# main.net
KiCad netlist of a schematic drawn in EAGLE
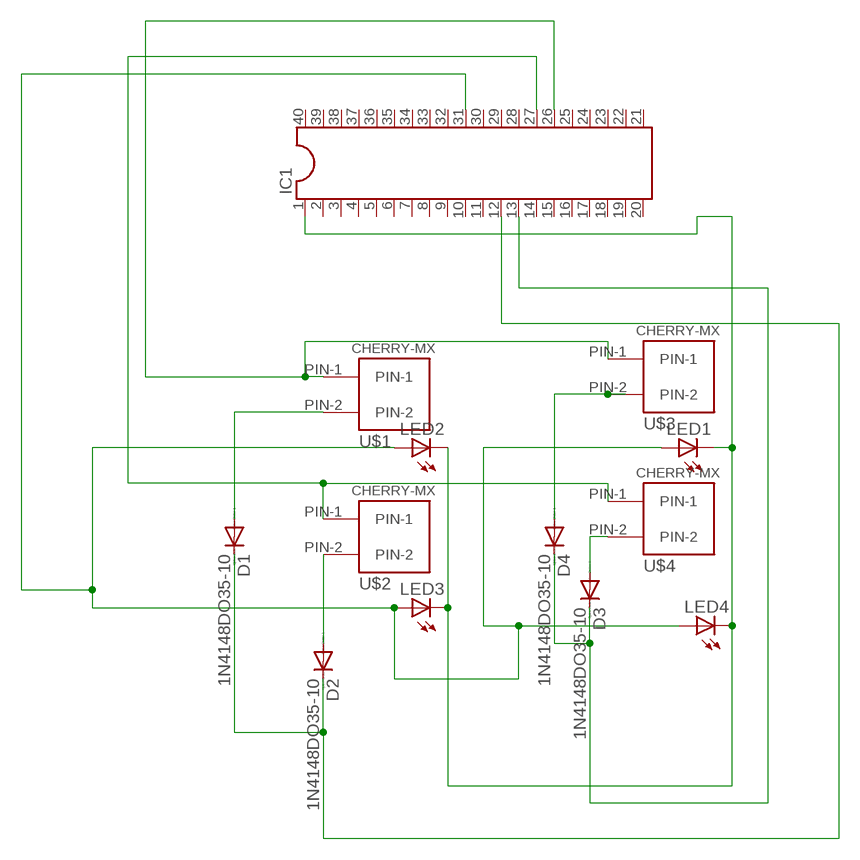
[diagram p0: schematic, sheet 1]

(export (version "E")
  (design (tool "Eeschema 10.0.6"))
  (components
    (comp (ref "D1")
      (value "1N4148DO35-10")
      (footprint "eagle-import:DO35-10")
      (libsource (lib "eagle-import") (part "1N4148DO35-10"))
    )
    (comp (ref "D2")
      (value "1N4148DO35-10")
      (footprint "eagle-import:DO35-10")
      (libsource (lib "eagle-import") (part "1N4148DO35-10"))
    )
    (comp (ref "D3")
      (value "1N4148DO35-10")
      (footprint "eagle-import:DO35-10")
      (libsource (lib "eagle-import") (part "1N4148DO35-10"))
    )
    (comp (ref "D4")
      (value "1N4148DO35-10")
      (footprint "eagle-import:DO35-10")
      (libsource (lib "eagle-import") (part "1N4148DO35-10"))
    )
    (comp (ref "IC1")
      (value "DIL40")
      (footprint "eagle-import:DIL40")
      (libsource (lib "eagle-import") (part "DIL40"))
    )
    (comp (ref "LED1")
      (value "LED3MM")
      (footprint "eagle-import:LED3MM")
      (libsource (lib "eagle-import") (part "LED3MM"))
    )
    (comp (ref "LED2")
      (value "LED3MM")
      (footprint "eagle-import:LED3MM")
      (libsource (lib "eagle-import") (part "LED3MM"))
    )
    (comp (ref "LED3")
      (value "LED3MM")
      (footprint "eagle-import:LED3MM")
      (libsource (lib "eagle-import") (part "LED3MM"))
    )
    (comp (ref "LED4")
      (value "LED3MM")
      (footprint "eagle-import:LED3MM")
      (libsource (lib "eagle-import") (part "LED3MM"))
    )
    (comp (ref "U$1")
      (value "CHERRY-MX-I")
      (footprint "eagle-import:CHERRY-MX-I")
      (libsource (lib "eagle-import") (part "CHERRY-MX-I"))
    )
    (comp (ref "U$2")
      (value "CHERRY-MX-I")
      (footprint "eagle-import:CHERRY-MX-I")
      (libsource (lib "eagle-import") (part "CHERRY-MX-I"))
    )
    (comp (ref "U$3")
      (value "CHERRY-MX-I")
      (footprint "eagle-import:CHERRY-MX-I")
      (libsource (lib "eagle-import") (part "CHERRY-MX-I"))
    )
    (comp (ref "U$4")
      (value "CHERRY-MX-I")
      (footprint "eagle-import:CHERRY-MX-I")
      (libsource (lib "eagle-import") (part "CHERRY-MX-I"))
    )
  )
  (nets
    (net (code "1") (name "Net-(D1-PadA)") (class "Default")
      (node (ref "D1") (pin "A") (pinfunction "A_A") (pintype "passive"))
      (node (ref "U$1") (pin "PIN-2") (pinfunction "PIN-2_PIN-2") (pintype "bidirectional"))
    )
    (net (code "2") (name "Net-(D1-PadC)") (class "Default")
      (node (ref "D1") (pin "C") (pinfunction "C_C") (pintype "passive"))
      (node (ref "D2") (pin "C") (pinfunction "C_C") (pintype "passive"))
      (node (ref "IC1") (pin "12") (pinfunction "12_12") (pintype "passive"))
    )
    (net (code "3") (name "Net-(D2-PadA)") (class "Default")
      (node (ref "D2") (pin "A") (pinfunction "A_A") (pintype "passive"))
      (node (ref "U$2") (pin "PIN-2") (pinfunction "PIN-2_PIN-2") (pintype "bidirectional"))
    )
    (net (code "4") (name "Net-(D3-PadA)") (class "Default")
      (node (ref "D3") (pin "A") (pinfunction "A_A") (pintype "passive"))
      (node (ref "U$4") (pin "PIN-2") (pinfunction "PIN-2_PIN-2") (pintype "bidirectional"))
    )
    (net (code "5") (name "Net-(D3-PadC)") (class "Default")
      (node (ref "D3") (pin "C") (pinfunction "C_C") (pintype "passive"))
      (node (ref "D4") (pin "C") (pinfunction "C_C") (pintype "passive"))
      (node (ref "IC1") (pin "13") (pinfunction "13_13") (pintype "passive"))
    )
    (net (code "6") (name "Net-(D4-PadA)") (class "Default")
      (node (ref "D4") (pin "A") (pinfunction "A_A") (pintype "passive"))
      (node (ref "U$3") (pin "PIN-2") (pinfunction "PIN-2_PIN-2") (pintype "bidirectional"))
    )
    (net (code "7") (name "Net-(IC1-Pad26)") (class "Default")
      (node (ref "IC1") (pin "26") (pinfunction "26_26") (pintype "passive"))
      (node (ref "U$1") (pin "PIN-1") (pinfunction "PIN-1_PIN-1") (pintype "bidirectional"))
      (node (ref "U$3") (pin "PIN-1") (pinfunction "PIN-1_PIN-1") (pintype "bidirectional"))
    )
    (net (code "8") (name "Net-(IC1-Pad27)") (class "Default")
      (node (ref "IC1") (pin "27") (pinfunction "27_27") (pintype "passive"))
      (node (ref "U$2") (pin "PIN-1") (pinfunction "PIN-1_PIN-1") (pintype "bidirectional"))
      (node (ref "U$4") (pin "PIN-1") (pinfunction "PIN-1_PIN-1") (pintype "bidirectional"))
    )
    (net (code "9") (name "Net-(IC1-Pad31)") (class "Default")
      (node (ref "IC1") (pin "31") (pinfunction "31_31") (pintype "passive"))
      (node (ref "LED1") (pin "A") (pinfunction "A_A") (pintype "passive"))
      (node (ref "LED2") (pin "A") (pinfunction "A_A") (pintype "passive"))
      (node (ref "LED3") (pin "A") (pinfunction "A_A") (pintype "passive"))
      (node (ref "LED4") (pin "A") (pinfunction "A_A") (pintype "passive"))
    )
    (net (code "10") (name "Net-(LED1-C)") (class "Default")
      (node (ref "IC1") (pin "1") (pinfunction "1_1") (pintype "passive"))
      (node (ref "LED1") (pin "K") (pinfunction "C_K") (pintype "passive"))
      (node (ref "LED2") (pin "K") (pinfunction "C_K") (pintype "passive"))
      (node (ref "LED3") (pin "K") (pinfunction "C_K") (pintype "passive"))
      (node (ref "LED4") (pin "K") (pinfunction "C_K") (pintype "passive"))
    )
    (net (code "11") (name "unconnected-(IC1-Pad2)") (class "Default")
      (node (ref "IC1") (pin "2") (pinfunction "2_2") (pintype "passive"))
    )
    (net (code "12") (name "unconnected-(IC1-Pad3)") (class "Default")
      (node (ref "IC1") (pin "3") (pinfunction "3_3") (pintype "passive"))
    )
    (net (code "13") (name "unconnected-(IC1-Pad4)") (class "Default")
      (node (ref "IC1") (pin "4") (pinfunction "4_4") (pintype "passive"))
    )
    (net (code "14") (name "unconnected-(IC1-Pad5)") (class "Default")
      (node (ref "IC1") (pin "5") (pinfunction "5_5") (pintype "passive"))
    )
    (net (code "15") (name "unconnected-(IC1-Pad6)") (class "Default")
      (node (ref "IC1") (pin "6") (pinfunction "6_6") (pintype "passive"))
    )
    (net (code "16") (name "unconnected-(IC1-Pad7)") (class "Default")
      (node (ref "IC1") (pin "7") (pinfunction "7_7") (pintype "passive"))
    )
    (net (code "17") (name "unconnected-(IC1-Pad8)") (class "Default")
      (node (ref "IC1") (pin "8") (pinfunction "8_8") (pintype "passive"))
    )
    (net (code "18") (name "unconnected-(IC1-Pad9)") (class "Default")
      (node (ref "IC1") (pin "9") (pinfunction "9_9") (pintype "passive"))
    )
    (net (code "19") (name "unconnected-(IC1-Pad10)") (class "Default")
      (node (ref "IC1") (pin "10") (pinfunction "10_10") (pintype "passive"))
    )
    (net (code "20") (name "unconnected-(IC1-Pad11)") (class "Default")
      (node (ref "IC1") (pin "11") (pinfunction "11_11") (pintype "passive"))
    )
    (net (code "21") (name "unconnected-(IC1-Pad14)") (class "Default")
      (node (ref "IC1") (pin "14") (pinfunction "14_14") (pintype "passive"))
    )
    (net (code "22") (name "unconnected-(IC1-Pad15)") (class "Default")
      (node (ref "IC1") (pin "15") (pinfunction "15_15") (pintype "passive"))
    )
    (net (code "23") (name "unconnected-(IC1-Pad16)") (class "Default")
      (node (ref "IC1") (pin "16") (pinfunction "16_16") (pintype "passive"))
    )
    (net (code "24") (name "unconnected-(IC1-Pad17)") (class "Default")
      (node (ref "IC1") (pin "17") (pinfunction "17_17") (pintype "passive"))
    )
    (net (code "25") (name "unconnected-(IC1-Pad18)") (class "Default")
      (node (ref "IC1") (pin "18") (pinfunction "18_18") (pintype "passive"))
    )
    (net (code "26") (name "unconnected-(IC1-Pad19)") (class "Default")
      (node (ref "IC1") (pin "19") (pinfunction "19_19") (pintype "passive"))
    )
    (net (code "27") (name "unconnected-(IC1-Pad20)") (class "Default")
      (node (ref "IC1") (pin "20") (pinfunction "20_20") (pintype "passive"))
    )
    (net (code "28") (name "unconnected-(IC1-Pad21)") (class "Default")
      (node (ref "IC1") (pin "21") (pinfunction "21_21") (pintype "passive"))
    )
    (net (code "29") (name "unconnected-(IC1-Pad22)") (class "Default")
      (node (ref "IC1") (pin "22") (pinfunction "22_22") (pintype "passive"))
    )
    (net (code "30") (name "unconnected-(IC1-Pad23)") (class "Default")
      (node (ref "IC1") (pin "23") (pinfunction "23_23") (pintype "passive"))
    )
    (net (code "31") (name "unconnected-(IC1-Pad24)") (class "Default")
      (node (ref "IC1") (pin "24") (pinfunction "24_24") (pintype "passive"))
    )
    (net (code "32") (name "unconnected-(IC1-Pad25)") (class "Default")
      (node (ref "IC1") (pin "25") (pinfunction "25_25") (pintype "passive"))
    )
    (net (code "33") (name "unconnected-(IC1-Pad28)") (class "Default")
      (node (ref "IC1") (pin "28") (pinfunction "28_28") (pintype "passive"))
    )
    (net (code "34") (name "unconnected-(IC1-Pad29)") (class "Default")
      (node (ref "IC1") (pin "29") (pinfunction "29_29") (pintype "passive"))
    )
    (net (code "35") (name "unconnected-(IC1-Pad30)") (class "Default")
      (node (ref "IC1") (pin "30") (pinfunction "30_30") (pintype "passive"))
    )
    (net (code "36") (name "unconnected-(IC1-Pad32)") (class "Default")
      (node (ref "IC1") (pin "32") (pinfunction "32_32") (pintype "passive"))
    )
    (net (code "37") (name "unconnected-(IC1-Pad33)") (class "Default")
      (node (ref "IC1") (pin "33") (pinfunction "33_33") (pintype "passive"))
    )
    (net (code "38") (name "unconnected-(IC1-Pad34)") (class "Default")
      (node (ref "IC1") (pin "34") (pinfunction "34_34") (pintype "passive"))
    )
    (net (code "39") (name "unconnected-(IC1-Pad35)") (class "Default")
      (node (ref "IC1") (pin "35") (pinfunction "35_35") (pintype "passive"))
    )
    (net (code "40") (name "unconnected-(IC1-Pad36)") (class "Default")
      (node (ref "IC1") (pin "36") (pinfunction "36_36") (pintype "passive"))
    )
    (net (code "41") (name "unconnected-(IC1-Pad37)") (class "Default")
      (node (ref "IC1") (pin "37") (pinfunction "37_37") (pintype "passive"))
    )
    (net (code "42") (name "unconnected-(IC1-Pad38)") (class "Default")
      (node (ref "IC1") (pin "38") (pinfunction "38_38") (pintype "passive"))
    )
    (net (code "43") (name "unconnected-(IC1-Pad39)") (class "Default")
      (node (ref "IC1") (pin "39") (pinfunction "39_39") (pintype "passive"))
    )
    (net (code "44") (name "unconnected-(IC1-Pad40)") (class "Default")
      (node (ref "IC1") (pin "40") (pinfunction "40_40") (pintype "passive"))
    )
  )
)
